# hibrido.net
KiCad netlist of a schematic drawn in EAGLE
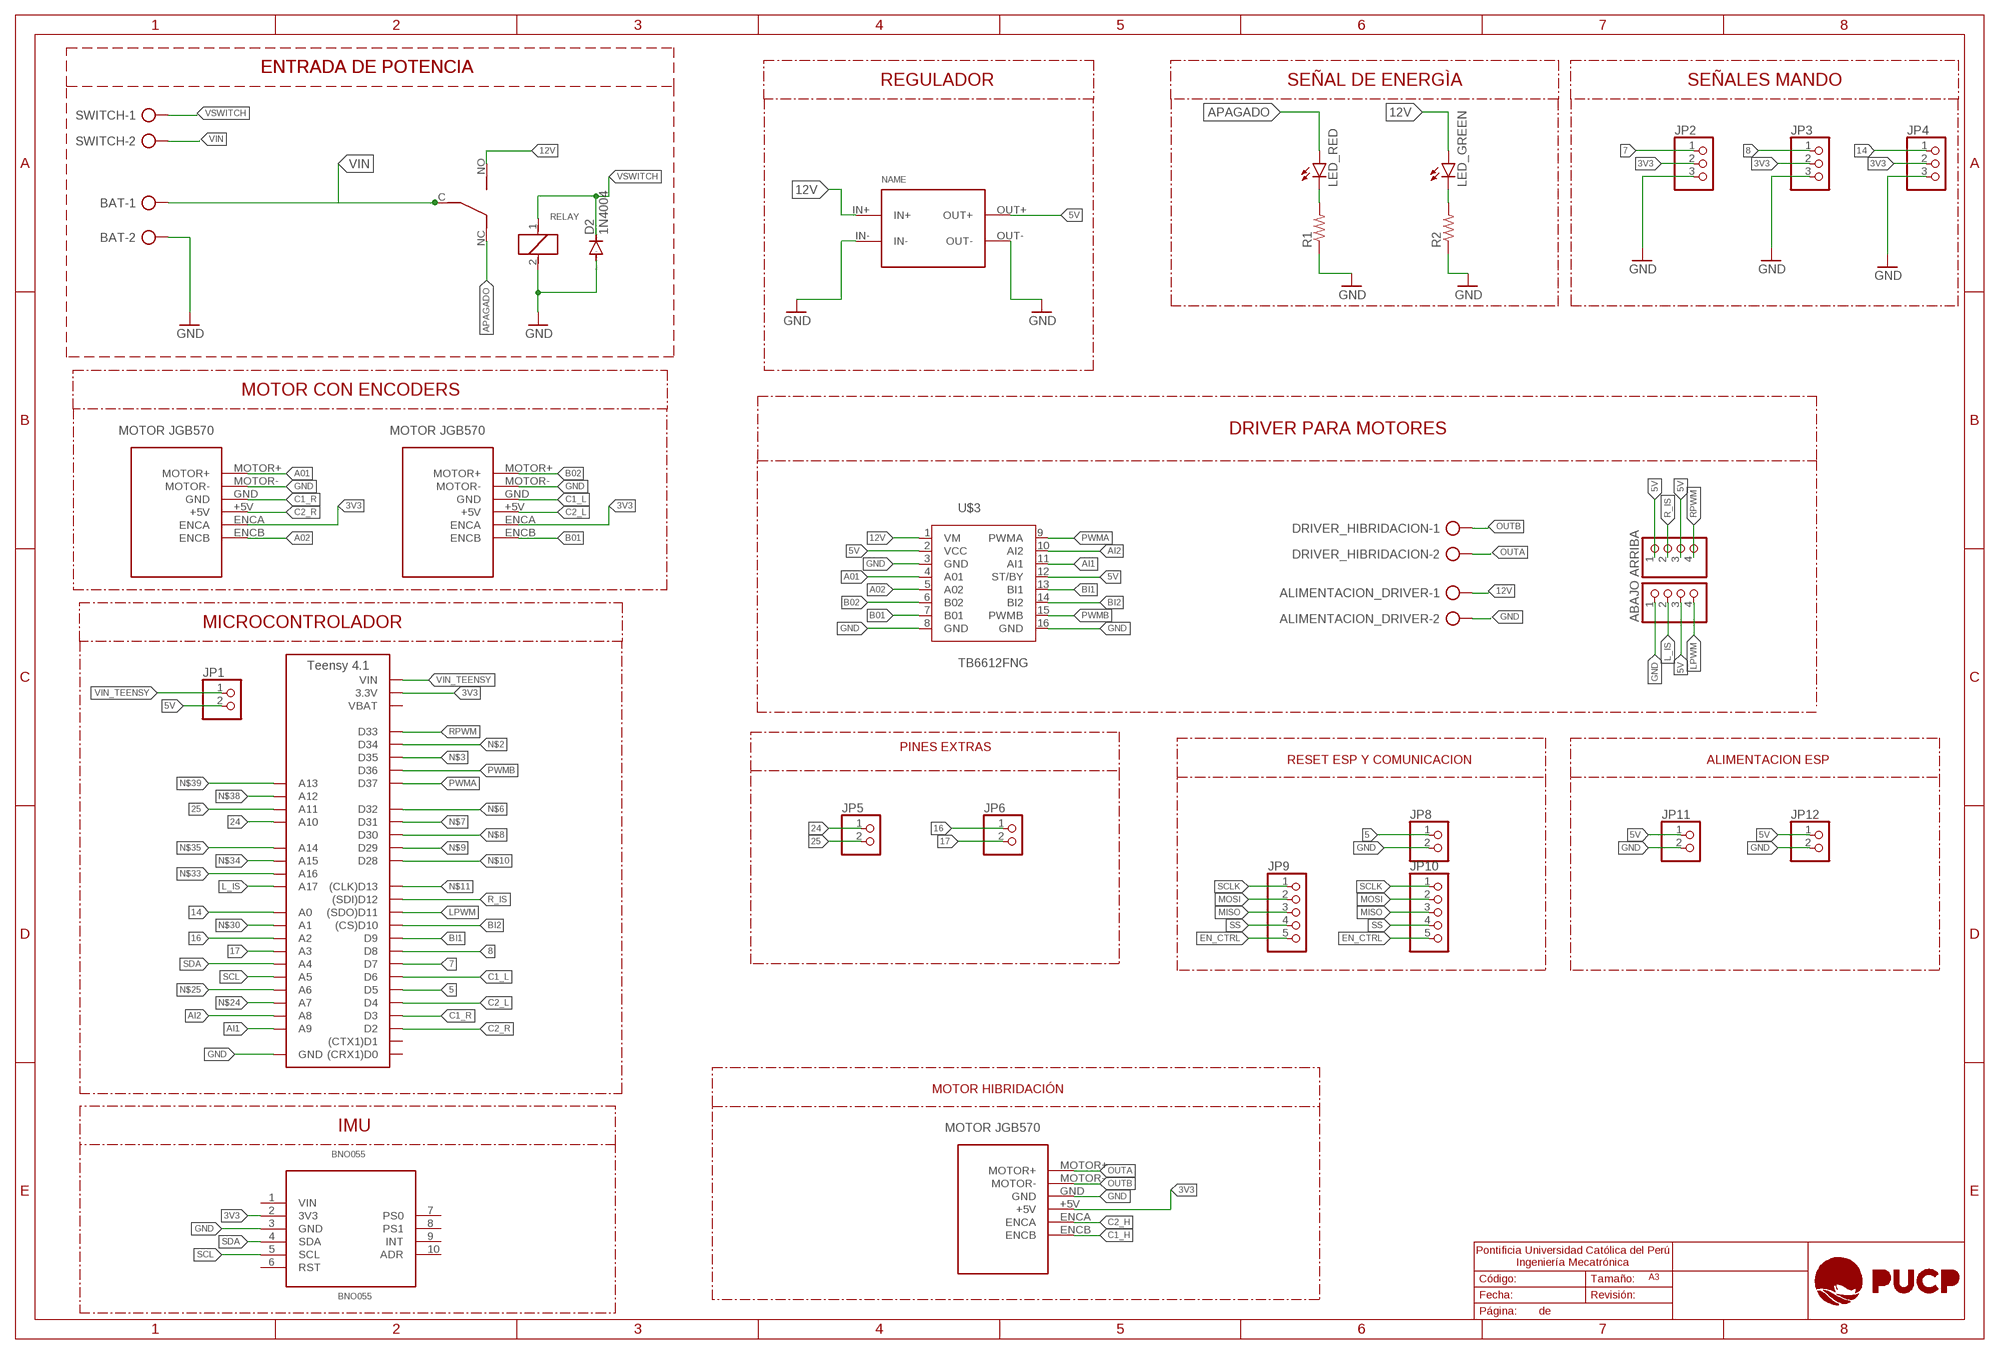
[diagram p0: schematic, sheet 1]

(export (version "E")
  (design (tool "Eeschema 10.0.6"))
  (components
    (comp (ref "A1")
      (value "TEENSY_4.1")
      (footprint "eagle-import:TEENSY_LONG_EXT")
      (fields (field (name "MF") "PJRC") (field (name "MP") "Teensy 4.1"))
      (libsource (lib "eagle-import") (part "TEENSY_4.1"))
    )
    (comp (ref "ABAJO")
      (value "PINHD-1X4")
      (footprint "eagle-import:1X04")
      (libsource (lib "eagle-import") (part "PINHD-1X4"))
    )
    (comp (ref "ALIMENTACION_DRIVER")
      (value "AK500/2-H")
      (footprint "eagle-import:AK500_2-H")
      (libsource (lib "eagle-import") (part "AK500/2-H"))
    )
    (comp (ref "ARRIBA")
      (value "PINHD-1X4")
      (footprint "eagle-import:1X04")
      (libsource (lib "eagle-import") (part "PINHD-1X4"))
    )
    (comp (ref "BAT")
      (value "AK500/2-H")
      (footprint "eagle-import:AK500_2-H")
      (libsource (lib "eagle-import") (part "AK500/2-H"))
    )
    (comp (ref "BNO055")
      (value "BNO055")
      (footprint "eagle-import:BNO055")
      (libsource (lib "eagle-import") (part "BNO055"))
    )
    (comp (ref "D2")
      (value "1N4004")
      (footprint "eagle-import:DO41-10")
      (libsource (lib "eagle-import") (part "1N4004"))
    )
    (comp (ref "DRIVER_HIBRIDACION")
      (value "AK500/2-H")
      (footprint "eagle-import:AK500_2-H")
      (libsource (lib "eagle-import") (part "AK500/2-H"))
    )
    (comp (ref "JP1")
      (value "PINHD-1X2")
      (footprint "eagle-import:1X02")
      (libsource (lib "eagle-import") (part "PINHD-1X2"))
    )
    (comp (ref "JP2")
      (value "PINHD-1X3")
      (footprint "eagle-import:1X03")
      (libsource (lib "eagle-import") (part "PINHD-1X3"))
    )
    (comp (ref "JP3")
      (value "PINHD-1X3")
      (footprint "eagle-import:1X03")
      (libsource (lib "eagle-import") (part "PINHD-1X3"))
    )
    (comp (ref "JP4")
      (value "PINHD-1X3")
      (footprint "eagle-import:1X03")
      (libsource (lib "eagle-import") (part "PINHD-1X3"))
    )
    (comp (ref "JP5")
      (value "PINHD-1X2")
      (footprint "eagle-import:1X02")
      (libsource (lib "eagle-import") (part "PINHD-1X2"))
    )
    (comp (ref "JP6")
      (value "PINHD-1X2")
      (footprint "eagle-import:1X02")
      (libsource (lib "eagle-import") (part "PINHD-1X2"))
    )
    (comp (ref "JP8")
      (value "PINHD-1X2")
      (footprint "eagle-import:1X02")
      (libsource (lib "eagle-import") (part "PINHD-1X2"))
    )
    (comp (ref "JP9")
      (value "PINHD-1X5")
      (footprint "eagle-import:1X05")
      (libsource (lib "eagle-import") (part "PINHD-1X5"))
    )
    (comp (ref "JP10")
      (value "PINHD-1X5")
      (footprint "eagle-import:1X05")
      (libsource (lib "eagle-import") (part "PINHD-1X5"))
    )
    (comp (ref "JP11")
      (value "PINHD-1X2")
      (footprint "eagle-import:1X02")
      (libsource (lib "eagle-import") (part "PINHD-1X2"))
    )
    (comp (ref "JP12")
      (value "PINHD-1X2")
      (footprint "eagle-import:1X02")
      (libsource (lib "eagle-import") (part "PINHD-1X2"))
    )
    (comp (ref "LED_GREEN")
      (value "LED5MM")
      (footprint "eagle-import:LED5MM")
      (libsource (lib "eagle-import") (part "LED5MM"))
    )
    (comp (ref "LED_RED")
      (value "LED5MM")
      (footprint "eagle-import:LED5MM")
      (libsource (lib "eagle-import") (part "LED5MM"))
    )
    (comp (ref "MOTOR1")
      (value "MOTOR_JGB370")
      (footprint "eagle-import:MOTOR_JGB370")
      (libsource (lib "eagle-import") (part "MOTOR_JGB370"))
    )
    (comp (ref "MOTOR3")
      (value "MOTOR_JGB370")
      (footprint "eagle-import:MOTOR_JGB370")
      (libsource (lib "eagle-import") (part "MOTOR_JGB370"))
    )
    (comp (ref "MOTOR5")
      (value "MOTOR_JGB370")
      (footprint "eagle-import:MOTOR_JGB370")
      (libsource (lib "eagle-import") (part "MOTOR_JGB370"))
    )
    (comp (ref "R1")
      (value "R-US_0207/10")
      (footprint "eagle-import:0207_10")
      (libsource (lib "eagle-import") (part "R-US_0207/10"))
    )
    (comp (ref "R2")
      (value "R-US_0207/10")
      (footprint "eagle-import:0207_10")
      (libsource (lib "eagle-import") (part "R-US_0207/10"))
    )
    (comp (ref "REG")
      (value "CP8-ADJ")
      (footprint "eagle-import:CP8-ADJ")
      (fields (field (name "SPICEPREFIX") "E"))
      (libsource (lib "eagle-import") (part "CP8-ADJ"))
    )
    (comp (ref "RELAY")
      (value "RELAY12V")
      (footprint "eagle-import:RELAY12V")
      (libsource (lib "eagle-import") (part "RELAY12V"))
    )
    (comp (ref "SWITCH")
      (value "AK500/2-H")
      (footprint "eagle-import:AK500_2-H")
      (libsource (lib "eagle-import") (part "AK500/2-H"))
    )
    (comp (ref "U$3")
      (value "TB6612FNG")
      (footprint "eagle-import:TB6612FNG")
      (libsource (lib "eagle-import") (part "TB6612FNG"))
    )
  )
  (nets
    (net (code "1") (name "/VBAT") (class "Default")
      (node (ref "A1") (pin "VBAT") (pinfunction "VBAT_VBAT") (pintype "power_in"))
    )
    (net (code "2") (name "3V3") (class "Default")
      (node (ref "A1") (pin "3V3") (pinfunction "3.3V_3V3") (pintype "power_in"))
      (node (ref "A1") (pin "3V3@2") (pinfunction "3.3V_3V3@2") (pintype "power_in"))
      (node (ref "A1") (pin "3V3@3") (pinfunction "3.3V_3V3@3") (pintype "power_in"))
      (node (ref "BNO055") (pin "2") (pinfunction "3V3_2") (pintype "bidirectional"))
      (node (ref "JP2") (pin "2") (pinfunction "2_2") (pintype "passive"))
      (node (ref "JP3") (pin "2") (pinfunction "2_2") (pintype "passive"))
      (node (ref "JP4") (pin "2") (pinfunction "2_2") (pintype "passive"))
      (node (ref "MOTOR1") (pin "+5V") (pinfunction "+5V_+5V") (pintype "bidirectional"))
      (node (ref "MOTOR3") (pin "ENCA") (pinfunction "ENCA_ENCA") (pintype "bidirectional"))
      (node (ref "MOTOR5") (pin "ENCA") (pinfunction "ENCA_ENCA") (pintype "bidirectional"))
    )
    (net (code "3") (name "5") (class "Default")
      (node (ref "A1") (pin "D5") (pinfunction "D5_D5") (pintype "bidirectional"))
      (node (ref "JP8") (pin "1") (pinfunction "1_1") (pintype "passive"))
    )
    (net (code "4") (name "5V") (class "Default")
      (node (ref "ABAJO") (pin "3") (pinfunction "3_3") (pintype "passive"))
      (node (ref "ARRIBA") (pin "1") (pinfunction "1_1") (pintype "passive"))
      (node (ref "ARRIBA") (pin "3") (pinfunction "3_3") (pintype "passive"))
      (node (ref "JP1") (pin "2") (pinfunction "2_2") (pintype "passive"))
      (node (ref "JP11") (pin "1") (pinfunction "1_1") (pintype "passive"))
      (node (ref "JP12") (pin "1") (pinfunction "1_1") (pintype "passive"))
      (node (ref "REG") (pin "OUT+") (pinfunction "OUT+_OUT+") (pintype "passive"))
      (node (ref "U$3") (pin "12") (pinfunction "ST/BY_12") (pintype "bidirectional"))
      (node (ref "U$3") (pin "2") (pinfunction "VCC_2") (pintype "bidirectional"))
    )
    (net (code "5") (name "7") (class "Default")
      (node (ref "A1") (pin "D7") (pinfunction "D7_D7") (pintype "bidirectional"))
      (node (ref "JP2") (pin "1") (pinfunction "1_1") (pintype "passive"))
    )
    (net (code "6") (name "8") (class "Default")
      (node (ref "A1") (pin "D8") (pinfunction "D8_D8") (pintype "bidirectional"))
      (node (ref "JP3") (pin "1") (pinfunction "1_1") (pintype "passive"))
    )
    (net (code "7") (name "12V") (class "Default")
      (node (ref "ALIMENTACION_DRIVER") (pin "1") (pinfunction "KL_1") (pintype "passive"))
      (node (ref "LED_GREEN") (pin "A") (pinfunction "A_A") (pintype "passive"))
      (node (ref "REG") (pin "IN+") (pinfunction "IN+_IN+") (pintype "passive"))
      (node (ref "RELAY") (pin "NO") (pinfunction "NO_NO") (pintype "passive"))
      (node (ref "U$3") (pin "1") (pinfunction "VM_1") (pintype "bidirectional"))
    )
    (net (code "8") (name "14") (class "Default")
      (node (ref "A1") (pin "D14") (pinfunction "A0_D14") (pintype "bidirectional"))
      (node (ref "JP4") (pin "1") (pinfunction "1_1") (pintype "passive"))
    )
    (net (code "9") (name "16") (class "Default")
      (node (ref "A1") (pin "D16") (pinfunction "A2_D16") (pintype "bidirectional"))
      (node (ref "JP6") (pin "1") (pinfunction "1_1") (pintype "passive"))
    )
    (net (code "10") (name "17") (class "Default")
      (node (ref "A1") (pin "D17") (pinfunction "A3_D17") (pintype "bidirectional"))
      (node (ref "JP6") (pin "2") (pinfunction "2_2") (pintype "passive"))
    )
    (net (code "11") (name "24") (class "Default")
      (node (ref "A1") (pin "D24") (pinfunction "A10_D24") (pintype "bidirectional"))
      (node (ref "JP5") (pin "1") (pinfunction "1_1") (pintype "passive"))
    )
    (net (code "12") (name "25") (class "Default")
      (node (ref "A1") (pin "D25") (pinfunction "A11_D25") (pintype "bidirectional"))
      (node (ref "JP5") (pin "2") (pinfunction "2_2") (pintype "passive"))
    )
    (net (code "13") (name "A01") (class "Default")
      (node (ref "MOTOR3") (pin "MOTOR+") (pinfunction "MOTOR+_MOTOR+") (pintype "bidirectional"))
      (node (ref "U$3") (pin "4") (pinfunction "A01_4") (pintype "bidirectional"))
    )
    (net (code "14") (name "A02") (class "Default")
      (node (ref "MOTOR3") (pin "ENCB") (pinfunction "ENCB_ENCB") (pintype "bidirectional"))
      (node (ref "U$3") (pin "5") (pinfunction "A02_5") (pintype "bidirectional"))
    )
    (net (code "15") (name "AI1") (class "Default")
      (node (ref "A1") (pin "D23") (pinfunction "A9_D23") (pintype "bidirectional"))
      (node (ref "U$3") (pin "11") (pinfunction "AI1_11") (pintype "bidirectional"))
    )
    (net (code "16") (name "AI2") (class "Default")
      (node (ref "A1") (pin "D22") (pinfunction "A8_D22") (pintype "bidirectional"))
      (node (ref "U$3") (pin "10") (pinfunction "AI2_10") (pintype "bidirectional"))
    )
    (net (code "17") (name "APAGADO") (class "Default")
      (node (ref "LED_RED") (pin "A") (pinfunction "A_A") (pintype "passive"))
      (node (ref "RELAY") (pin "NC") (pinfunction "NC_NC") (pintype "passive"))
    )
    (net (code "18") (name "B01") (class "Default")
      (node (ref "MOTOR5") (pin "ENCB") (pinfunction "ENCB_ENCB") (pintype "bidirectional"))
      (node (ref "U$3") (pin "7") (pinfunction "B01_7") (pintype "bidirectional"))
    )
    (net (code "19") (name "B02") (class "Default")
      (node (ref "MOTOR5") (pin "MOTOR+") (pinfunction "MOTOR+_MOTOR+") (pintype "bidirectional"))
      (node (ref "U$3") (pin "6") (pinfunction "B02_6") (pintype "bidirectional"))
    )
    (net (code "20") (name "BI1") (class "Default")
      (node (ref "A1") (pin "D9") (pinfunction "D9_D9") (pintype "bidirectional"))
      (node (ref "U$3") (pin "13") (pinfunction "BI1_13") (pintype "bidirectional"))
    )
    (net (code "21") (name "BI2") (class "Default")
      (node (ref "A1") (pin "D10") (pinfunction "(CS)D10_D10") (pintype "bidirectional"))
      (node (ref "U$3") (pin "14") (pinfunction "BI2_14") (pintype "bidirectional"))
    )
    (net (code "22") (name "C1_H") (class "Default")
      (node (ref "MOTOR1") (pin "ENCB") (pinfunction "ENCB_ENCB") (pintype "bidirectional"))
    )
    (net (code "23") (name "C1_L") (class "Default")
      (node (ref "A1") (pin "D6") (pinfunction "D6_D6") (pintype "bidirectional"))
      (node (ref "MOTOR5") (pin "GND") (pinfunction "GND_GND") (pintype "bidirectional"))
    )
    (net (code "24") (name "C1_R") (class "Default")
      (node (ref "A1") (pin "D3") (pinfunction "D3_D3") (pintype "bidirectional"))
      (node (ref "MOTOR3") (pin "GND") (pinfunction "GND_GND") (pintype "bidirectional"))
    )
    (net (code "25") (name "C2_H") (class "Default")
      (node (ref "MOTOR1") (pin "ENCA") (pinfunction "ENCA_ENCA") (pintype "bidirectional"))
    )
    (net (code "26") (name "C2_L") (class "Default")
      (node (ref "A1") (pin "D4") (pinfunction "D4_D4") (pintype "bidirectional"))
      (node (ref "MOTOR5") (pin "+5V") (pinfunction "+5V_+5V") (pintype "bidirectional"))
    )
    (net (code "27") (name "C2_R") (class "Default")
      (node (ref "A1") (pin "D2") (pinfunction "D2_D2") (pintype "bidirectional"))
      (node (ref "MOTOR3") (pin "+5V") (pinfunction "+5V_+5V") (pintype "bidirectional"))
    )
    (net (code "28") (name "EN_CTRL") (class "Default")
      (node (ref "JP10") (pin "5") (pinfunction "5_5") (pintype "passive"))
      (node (ref "JP9") (pin "5") (pinfunction "5_5") (pintype "passive"))
    )
    (net (code "29") (name "GND") (class "Default")
      (node (ref "A1") (pin "AGND/GND") (pinfunction "GND_AGND/GND") (pintype "bidirectional"))
      (node (ref "A1") (pin "GND") (pinfunction "GND_GND") (pintype "bidirectional"))
      (node (ref "A1") (pin "GND@2") (pinfunction "GND_GND@2") (pintype "bidirectional"))
      (node (ref "ABAJO") (pin "1") (pinfunction "1_1") (pintype "passive"))
      (node (ref "ALIMENTACION_DRIVER") (pin "2") (pinfunction "KL_2") (pintype "passive"))
      (node (ref "BAT") (pin "2") (pinfunction "KL_2") (pintype "passive"))
      (node (ref "BNO055") (pin "3") (pinfunction "GND_3") (pintype "bidirectional"))
      (node (ref "D2") (pin "A") (pinfunction "A_A") (pintype "passive"))
      (node (ref "JP11") (pin "2") (pinfunction "2_2") (pintype "passive"))
      (node (ref "JP12") (pin "2") (pinfunction "2_2") (pintype "passive"))
      (node (ref "JP2") (pin "3") (pinfunction "3_3") (pintype "passive"))
      (node (ref "JP3") (pin "3") (pinfunction "3_3") (pintype "passive"))
      (node (ref "JP4") (pin "3") (pinfunction "3_3") (pintype "passive"))
      (node (ref "JP8") (pin "2") (pinfunction "2_2") (pintype "passive"))
      (node (ref "MOTOR1") (pin "GND") (pinfunction "GND_GND") (pintype "bidirectional"))
      (node (ref "MOTOR3") (pin "MOTOR-") (pinfunction "MOTOR-_MOTOR-") (pintype "bidirectional"))
      (node (ref "MOTOR5") (pin "MOTOR-") (pinfunction "MOTOR-_MOTOR-") (pintype "bidirectional"))
      (node (ref "R1") (pin "1") (pinfunction "1_1") (pintype "passive"))
      (node (ref "R2") (pin "1") (pinfunction "1_1") (pintype "passive"))
      (node (ref "REG") (pin "IN-") (pinfunction "IN-_IN-") (pintype "passive"))
      (node (ref "REG") (pin "OUT-") (pinfunction "OUT-_OUT-") (pintype "passive"))
      (node (ref "RELAY") (pin "2") (pinfunction "2_2") (pintype "passive"))
      (node (ref "U$3") (pin "16") (pinfunction "GND_16") (pintype "bidirectional"))
      (node (ref "U$3") (pin "3") (pinfunction "GND_3") (pintype "bidirectional"))
      (node (ref "U$3") (pin "8") (pinfunction "GND_8") (pintype "bidirectional"))
    )
    (net (code "30") (name "LPWM") (class "Default")
      (node (ref "A1") (pin "D11") (pinfunction "(SDO)D11_D11") (pintype "bidirectional"))
      (node (ref "ABAJO") (pin "4") (pinfunction "4_4") (pintype "passive"))
    )
    (net (code "31") (name "L_IS") (class "Default")
      (node (ref "A1") (pin "D41") (pinfunction "A17_D41") (pintype "bidirectional"))
      (node (ref "ABAJO") (pin "2") (pinfunction "2_2") (pintype "passive"))
    )
    (net (code "32") (name "MISO") (class "Default")
      (node (ref "JP10") (pin "3") (pinfunction "3_3") (pintype "passive"))
      (node (ref "JP9") (pin "3") (pinfunction "3_3") (pintype "passive"))
    )
    (net (code "33") (name "MOSI") (class "Default")
      (node (ref "JP10") (pin "2") (pinfunction "2_2") (pintype "passive"))
      (node (ref "JP9") (pin "2") (pinfunction "2_2") (pintype "passive"))
    )
    (net (code "34") (name "N$2") (class "Default")
      (node (ref "A1") (pin "D34") (pinfunction "D34_D34") (pintype "bidirectional"))
    )
    (net (code "35") (name "N$3") (class "Default")
      (node (ref "A1") (pin "D35") (pinfunction "D35_D35") (pintype "bidirectional"))
    )
    (net (code "36") (name "N$6") (class "Default")
      (node (ref "A1") (pin "D32") (pinfunction "D32_D32") (pintype "bidirectional"))
    )
    (net (code "37") (name "N$7") (class "Default")
      (node (ref "A1") (pin "D31") (pinfunction "D31_D31") (pintype "bidirectional"))
    )
    (net (code "38") (name "N$8") (class "Default")
      (node (ref "A1") (pin "D30") (pinfunction "D30_D30") (pintype "bidirectional"))
    )
    (net (code "39") (name "N$9") (class "Default")
      (node (ref "A1") (pin "D29") (pinfunction "D29_D29") (pintype "bidirectional"))
    )
    (net (code "40") (name "N$10") (class "Default")
      (node (ref "A1") (pin "D28") (pinfunction "D28_D28") (pintype "bidirectional"))
    )
    (net (code "41") (name "N$11") (class "Default")
      (node (ref "A1") (pin "D13") (pinfunction "(CLK)D13_D13") (pintype "bidirectional"))
    )
    (net (code "42") (name "N$24") (class "Default")
      (node (ref "A1") (pin "D21") (pinfunction "A7_D21") (pintype "bidirectional"))
    )
    (net (code "43") (name "N$25") (class "Default")
      (node (ref "A1") (pin "D20") (pinfunction "A6_D20") (pintype "bidirectional"))
    )
    (net (code "44") (name "N$30") (class "Default")
      (node (ref "A1") (pin "D15") (pinfunction "A1_D15") (pintype "bidirectional"))
    )
    (net (code "45") (name "N$33") (class "Default")
      (node (ref "A1") (pin "D40") (pinfunction "A16_D40") (pintype "bidirectional"))
    )
    (net (code "46") (name "N$34") (class "Default")
      (node (ref "A1") (pin "D39") (pinfunction "A15_D39") (pintype "bidirectional"))
    )
    (net (code "47") (name "N$35") (class "Default")
      (node (ref "A1") (pin "D38") (pinfunction "A14_D38") (pintype "bidirectional"))
    )
    (net (code "48") (name "N$38") (class "Default")
      (node (ref "A1") (pin "D26") (pinfunction "A12_D26") (pintype "bidirectional"))
    )
    (net (code "49") (name "N$39") (class "Default")
      (node (ref "A1") (pin "D27") (pinfunction "A13_D27") (pintype "bidirectional"))
    )
    (net (code "50") (name "Net-(LED_GREEN-C)") (class "Default")
      (node (ref "LED_GREEN") (pin "K") (pinfunction "C_K") (pintype "passive"))
      (node (ref "R2") (pin "2") (pinfunction "2_2") (pintype "passive"))
    )
    (net (code "51") (name "Net-(LED_RED-C)") (class "Default")
      (node (ref "LED_RED") (pin "K") (pinfunction "C_K") (pintype "passive"))
      (node (ref "R1") (pin "2") (pinfunction "2_2") (pintype "passive"))
    )
    (net (code "52") (name "OUTA") (class "Default")
      (node (ref "DRIVER_HIBRIDACION") (pin "2") (pinfunction "KL_2") (pintype "passive"))
      (node (ref "MOTOR1") (pin "MOTOR+") (pinfunction "MOTOR+_MOTOR+") (pintype "bidirectional"))
    )
    (net (code "53") (name "OUTB") (class "Default")
      (node (ref "DRIVER_HIBRIDACION") (pin "1") (pinfunction "KL_1") (pintype "passive"))
      (node (ref "MOTOR1") (pin "MOTOR-") (pinfunction "MOTOR-_MOTOR-") (pintype "bidirectional"))
    )
    (net (code "54") (name "PWMA") (class "Default")
      (node (ref "A1") (pin "D37") (pinfunction "D37_D37") (pintype "bidirectional"))
      (node (ref "U$3") (pin "9") (pinfunction "PWMA_9") (pintype "bidirectional"))
    )
    (net (code "55") (name "PWMB") (class "Default")
      (node (ref "A1") (pin "D36") (pinfunction "D36_D36") (pintype "bidirectional"))
      (node (ref "U$3") (pin "15") (pinfunction "PWMB_15") (pintype "bidirectional"))
    )
    (net (code "56") (name "RPWM") (class "Default")
      (node (ref "A1") (pin "D33") (pinfunction "D33_D33") (pintype "bidirectional"))
      (node (ref "ARRIBA") (pin "4") (pinfunction "4_4") (pintype "passive"))
    )
    (net (code "57") (name "R_IS") (class "Default")
      (node (ref "A1") (pin "D12") (pinfunction "(SDI)D12_D12") (pintype "bidirectional"))
      (node (ref "ARRIBA") (pin "2") (pinfunction "2_2") (pintype "passive"))
    )
    (net (code "58") (name "SCL") (class "Default")
      (node (ref "A1") (pin "D19") (pinfunction "A5_D19") (pintype "bidirectional"))
      (node (ref "BNO055") (pin "5") (pinfunction "SCL_5") (pintype "bidirectional"))
    )
    (net (code "59") (name "SCLK") (class "Default")
      (node (ref "JP10") (pin "1") (pinfunction "1_1") (pintype "passive"))
      (node (ref "JP9") (pin "1") (pinfunction "1_1") (pintype "passive"))
    )
    (net (code "60") (name "SDA") (class "Default")
      (node (ref "A1") (pin "D18") (pinfunction "A4_D18") (pintype "bidirectional"))
      (node (ref "BNO055") (pin "4") (pinfunction "SDA_4") (pintype "bidirectional"))
    )
    (net (code "61") (name "SS") (class "Default")
      (node (ref "JP10") (pin "4") (pinfunction "4_4") (pintype "passive"))
      (node (ref "JP9") (pin "4") (pinfunction "4_4") (pintype "passive"))
    )
    (net (code "62") (name "VIN") (class "Default")
      (node (ref "BAT") (pin "1") (pinfunction "KL_1") (pintype "passive"))
      (node (ref "RELAY") (pin "C") (pinfunction "C_C") (pintype "passive"))
      (node (ref "SWITCH") (pin "2") (pinfunction "KL_2") (pintype "passive"))
    )
    (net (code "63") (name "VIN_TEENSY") (class "Default")
      (node (ref "A1") (pin "VIN") (pinfunction "VIN_VIN") (pintype "power_in"))
      (node (ref "JP1") (pin "1") (pinfunction "1_1") (pintype "passive"))
    )
    (net (code "64") (name "VSWITCH") (class "Default")
      (node (ref "D2") (pin "C") (pinfunction "C_C") (pintype "passive"))
      (node (ref "RELAY") (pin "1") (pinfunction "1_1") (pintype "passive"))
      (node (ref "SWITCH") (pin "1") (pinfunction "KL_1") (pintype "passive"))
    )
    (net (code "65") (name "unconnected-(A1-(CRX1)D0-PadD0)") (class "Default")
      (node (ref "A1") (pin "D0") (pinfunction "(CRX1)D0_D0") (pintype "bidirectional"))
    )
    (net (code "66") (name "unconnected-(A1-(CTX1)D1-PadD1)") (class "Default")
      (node (ref "A1") (pin "D1") (pinfunction "(CTX1)D1_D1") (pintype "bidirectional"))
    )
    (net (code "67") (name "unconnected-(BNO055-ADR-Pad10)") (class "Default")
      (node (ref "BNO055") (pin "10") (pinfunction "ADR_10") (pintype "bidirectional"))
    )
    (net (code "68") (name "unconnected-(BNO055-INT-Pad9)") (class "Default")
      (node (ref "BNO055") (pin "9") (pinfunction "INT_9") (pintype "bidirectional"))
    )
    (net (code "69") (name "unconnected-(BNO055-PS0-Pad7)") (class "Default")
      (node (ref "BNO055") (pin "7") (pinfunction "PS0_7") (pintype "bidirectional"))
    )
    (net (code "70") (name "unconnected-(BNO055-PS1-Pad8)") (class "Default")
      (node (ref "BNO055") (pin "8") (pinfunction "PS1_8") (pintype "bidirectional"))
    )
    (net (code "71") (name "unconnected-(BNO055-RST-Pad6)") (class "Default")
      (node (ref "BNO055") (pin "6") (pinfunction "RST_6") (pintype "bidirectional"))
    )
    (net (code "72") (name "unconnected-(BNO055-VIN-Pad1)") (class "Default")
      (node (ref "BNO055") (pin "1") (pinfunction "VIN_1") (pintype "bidirectional"))
    )
  )
)
